# SimulatorT2MRSensorRevD.net
KiCad netlist of a schematic drawn in EAGLE
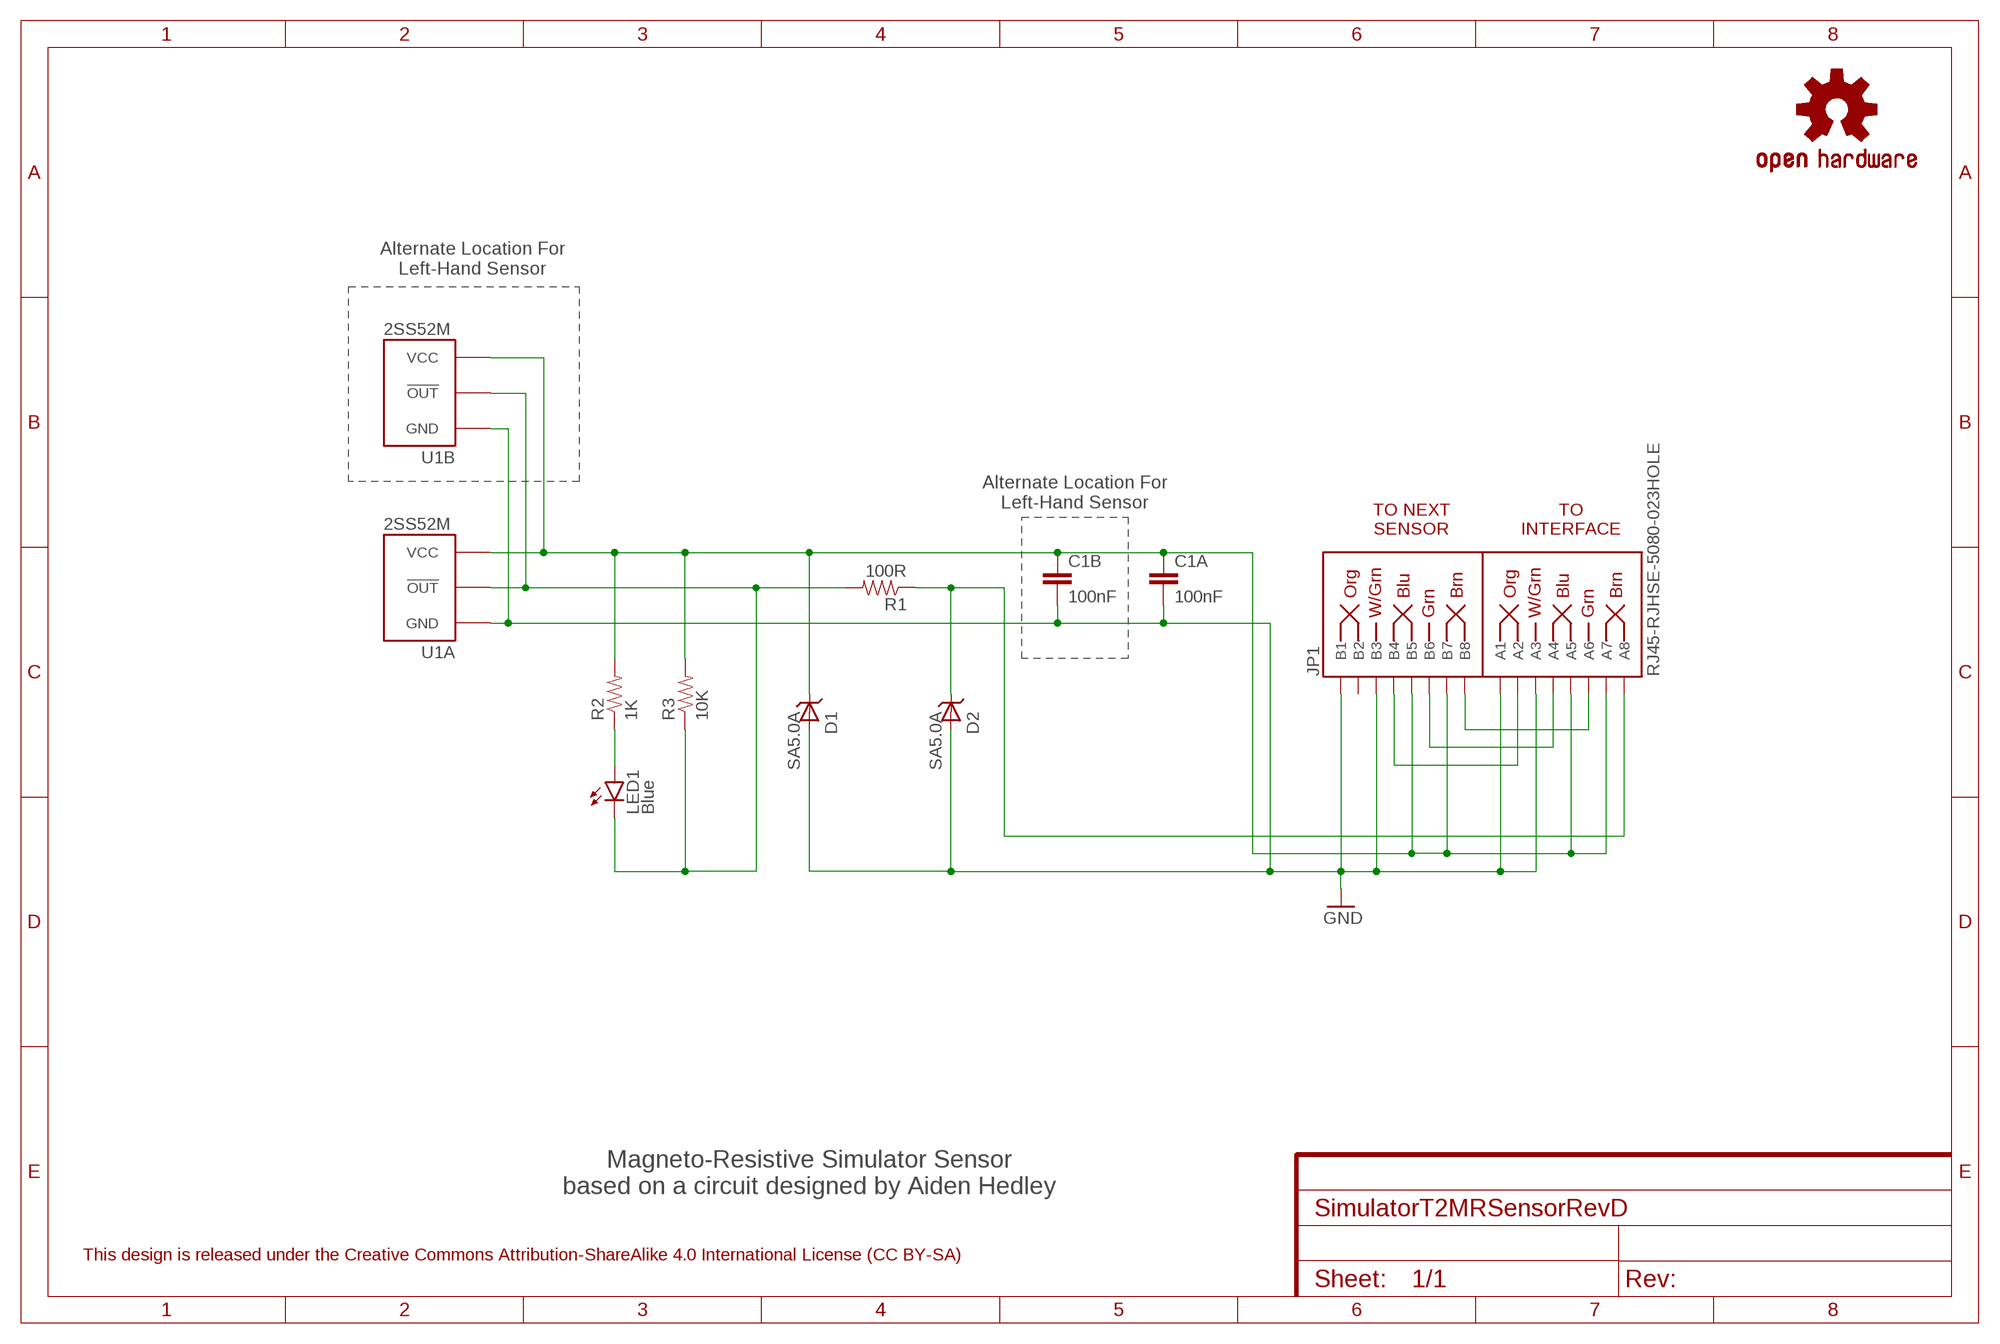
[diagram p0: schematic, sheet 1]

(export (version "E")
  (design (tool "Eeschema 10.0.6"))
  (components
    (comp (ref "C1A")
      (value "100nF")
      (footprint "eagle-import:CAP-PTH-SMALL")
      (libsource (lib "eagle-import") (part "CAPPTH"))
    )
    (comp (ref "C1B")
      (value "100nF")
      (footprint "eagle-import:CAP-PTH-SMALL")
      (libsource (lib "eagle-import") (part "CAPPTH"))
    )
    (comp (ref "D1")
      (value "SA5.0A")
      (footprint "eagle-import:DO41_TVS_UNI")
      (libsource (lib "eagle-import") (part "SA5.0A"))
    )
    (comp (ref "D2")
      (value "SA5.0A")
      (footprint "eagle-import:DO41_TVS_UNI")
      (libsource (lib "eagle-import") (part "SA5.0A"))
    )
    (comp (ref "JP1")
      (value "RJ45-RJHSE-5080-023HOLE")
      (footprint "eagle-import:RJ45-RJHSE-5080-02-3HOLE")
      (libsource (lib "eagle-import") (part "RJ45-RJHSE-5080-023HOLE"))
    )
    (comp (ref "LED1")
      (value "Blue")
      (footprint "eagle-import:LED3MM")
      (libsource (lib "eagle-import") (part "LED3MM"))
    )
    (comp (ref "LOGO1")
      (value "OSHW-LOGOS")
      (footprint "eagle-import:OSHW-LOGO-S")
      (libsource (lib "eagle-import") (part "OSHW-LOGOS"))
    )
    (comp (ref "R1")
      (value "100R")
      (footprint "eagle-import:AXIAL-0.4")
      (libsource (lib "eagle-import") (part "RESISTORPTH-1/4W"))
    )
    (comp (ref "R2")
      (value "1K")
      (footprint "eagle-import:AXIAL-0.4")
      (libsource (lib "eagle-import") (part "RESISTORPTH-1/4W"))
    )
    (comp (ref "R3")
      (value "10K")
      (footprint "eagle-import:AXIAL-0.4")
      (libsource (lib "eagle-import") (part "RESISTORPTH-1/4W"))
    )
    (comp (ref "U1A")
      (value "2SS52MOFFSET")
      (footprint "eagle-import:2SS52M_FLAT_OFFSET")
      (libsource (lib "eagle-import") (part "2SS52MOFFSET"))
    )
    (comp (ref "U1B")
      (value "2SS52MOFFSET")
      (footprint "eagle-import:2SS52M_FLAT_OFFSET")
      (libsource (lib "eagle-import") (part "2SS52MOFFSET"))
    )
  )
  (nets
    (net (code "1") (name "GND") (class "Default")
      (node (ref "C1A") (pin "2") (pinfunction "2_2") (pintype "passive"))
      (node (ref "C1B") (pin "2") (pinfunction "2_2") (pintype "passive"))
      (node (ref "D1") (pin "ANODE") (pinfunction "ANODE_ANODE") (pintype "passive"))
      (node (ref "D2") (pin "ANODE") (pinfunction "ANODE_ANODE") (pintype "passive"))
      (node (ref "JP1") (pin "A1") (pinfunction "A1_A1") (pintype "bidirectional"))
      (node (ref "JP1") (pin "A3") (pinfunction "A3_A3") (pintype "bidirectional"))
      (node (ref "JP1") (pin "B1") (pinfunction "B1_B1") (pintype "bidirectional"))
      (node (ref "JP1") (pin "B3") (pinfunction "B3_B3") (pintype "bidirectional"))
      (node (ref "U1A") (pin "P$1") (pinfunction "GND_P$1") (pintype "bidirectional"))
      (node (ref "U1B") (pin "P$1") (pinfunction "GND_P$1") (pintype "bidirectional"))
    )
    (net (code "2") (name "Net-(JP1-PadA2)") (class "Default")
      (node (ref "JP1") (pin "A2") (pinfunction "A2_A2") (pintype "bidirectional"))
      (node (ref "JP1") (pin "B4") (pinfunction "B4_B4") (pintype "bidirectional"))
    )
    (net (code "3") (name "Net-(JP1-PadA4)") (class "Default")
      (node (ref "JP1") (pin "A4") (pinfunction "A4_A4") (pintype "bidirectional"))
      (node (ref "JP1") (pin "B6") (pinfunction "B6_B6") (pintype "bidirectional"))
    )
    (net (code "4") (name "Net-(JP1-PadA6)") (class "Default")
      (node (ref "JP1") (pin "A6") (pinfunction "A6_A6") (pintype "bidirectional"))
      (node (ref "JP1") (pin "B8") (pinfunction "B8_B8") (pintype "bidirectional"))
    )
    (net (code "5") (name "Net-(LED1-C)") (class "Default")
      (node (ref "LED1") (pin "K") (pinfunction "C_K") (pintype "passive"))
      (node (ref "R1") (pin "P$2") (pinfunction "2_P$2") (pintype "passive"))
      (node (ref "R3") (pin "P$1") (pinfunction "1_P$1") (pintype "passive"))
      (node (ref "U1A") (pin "P$2") (pinfunction "~{OUT}_P$2") (pintype "bidirectional"))
      (node (ref "U1B") (pin "P$2") (pinfunction "~{OUT}_P$2") (pintype "bidirectional"))
    )
    (net (code "6") (name "Net-(R1-1)") (class "Default")
      (node (ref "D2") (pin "CATHODE") (pinfunction "CATHODE_CATHODE") (pintype "passive"))
      (node (ref "JP1") (pin "A8") (pinfunction "A8_A8") (pintype "bidirectional"))
      (node (ref "R1") (pin "P$1") (pinfunction "1_P$1") (pintype "passive"))
    )
    (net (code "7") (name "Net-(R2-1)") (class "Default")
      (node (ref "LED1") (pin "A") (pinfunction "A_A") (pintype "passive"))
      (node (ref "R2") (pin "P$1") (pinfunction "1_P$1") (pintype "passive"))
    )
    (net (code "8") (name "Net-(R2-2)") (class "Default")
      (node (ref "C1A") (pin "1") (pinfunction "1_1") (pintype "passive"))
      (node (ref "C1B") (pin "1") (pinfunction "1_1") (pintype "passive"))
      (node (ref "D1") (pin "CATHODE") (pinfunction "CATHODE_CATHODE") (pintype "passive"))
      (node (ref "JP1") (pin "A5") (pinfunction "A5_A5") (pintype "bidirectional"))
      (node (ref "JP1") (pin "A7") (pinfunction "A7_A7") (pintype "bidirectional"))
      (node (ref "JP1") (pin "B5") (pinfunction "B5_B5") (pintype "bidirectional"))
      (node (ref "JP1") (pin "B7") (pinfunction "B7_B7") (pintype "bidirectional"))
      (node (ref "R2") (pin "P$2") (pinfunction "2_P$2") (pintype "passive"))
      (node (ref "R3") (pin "P$2") (pinfunction "2_P$2") (pintype "passive"))
      (node (ref "U1A") (pin "P$3") (pinfunction "VCC_P$3") (pintype "bidirectional"))
      (node (ref "U1B") (pin "P$3") (pinfunction "VCC_P$3") (pintype "bidirectional"))
    )
    (net (code "9") (name "unconnected-(JP1-PadB2)") (class "Default")
      (node (ref "JP1") (pin "B2") (pinfunction "B2_B2") (pintype "bidirectional"))
    )
  )
)
